# 3_Reinforcing_properties_Frequency_chara.net
KiCad netlist of a schematic drawn in Altium Designer
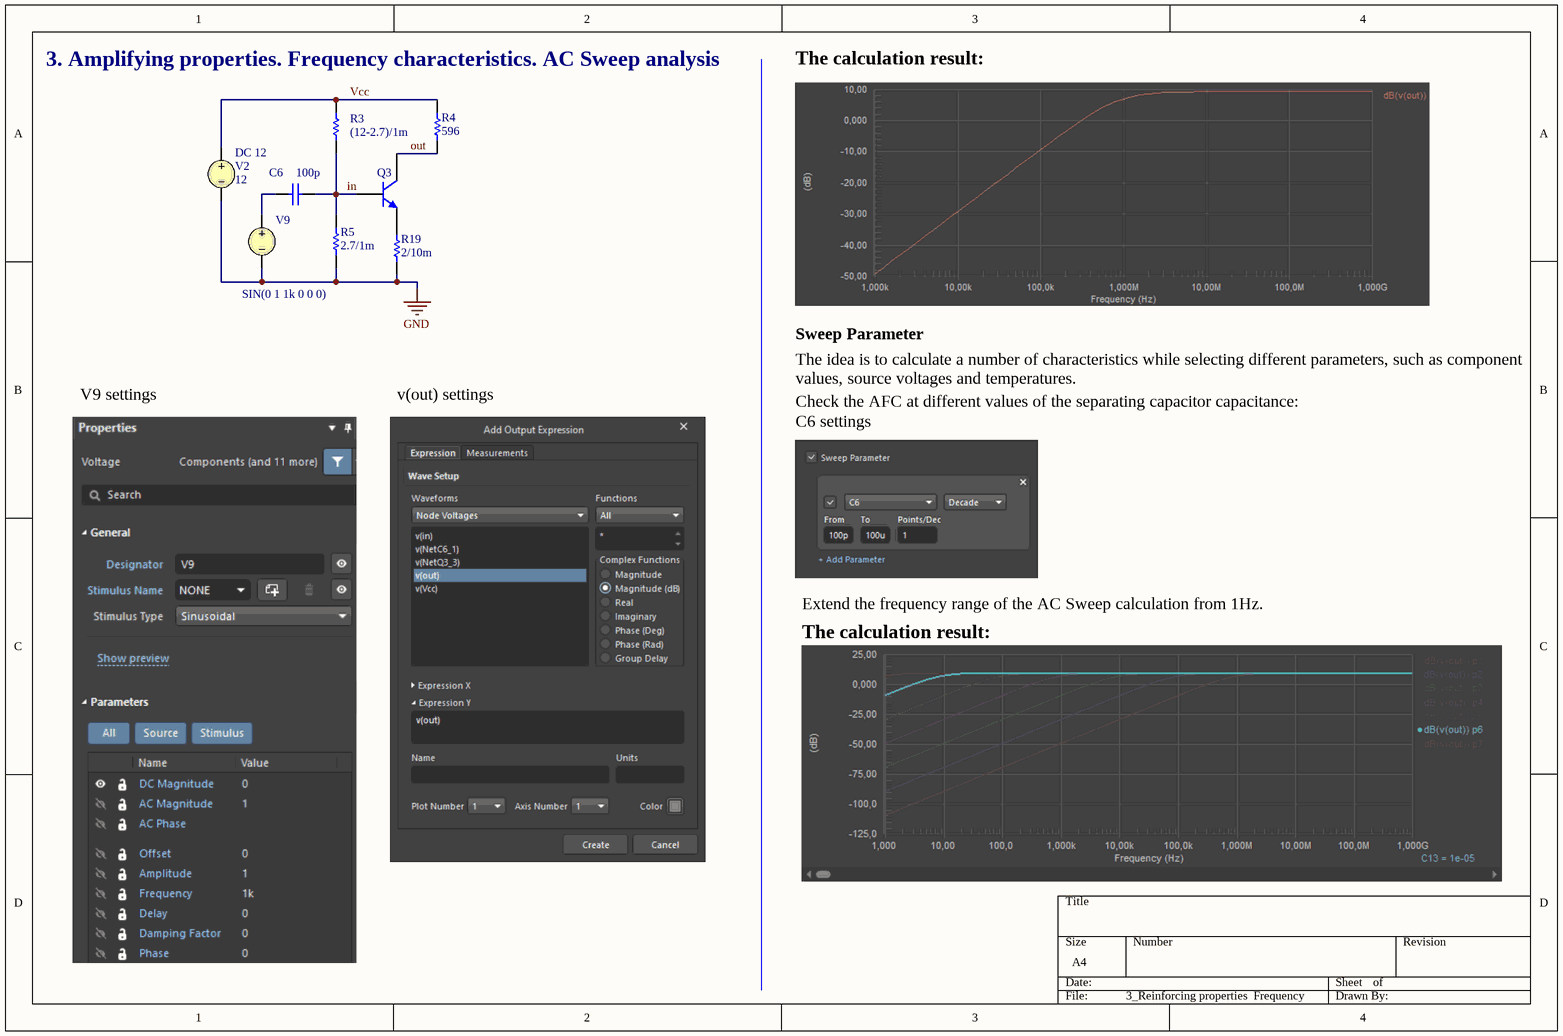
[diagram p0: 3_Reinforcing properties  Frequency characteristics.SchDoc]

(export (version "E")
  (design (tool "Eeschema 10.0.6"))
  (components
    (comp (ref "C6")
      (value "100p")
      (description "Capacitor")
      (libsource (lib "Simulation Generic Components") (part "Capacitor"))
    )
    (comp (ref "Q3")
      (value "Bipolar  NPN 3 Pins  Transistor  Modified Version of the Gummel-Poon Model")
      (libsource (lib "Simulation Generic Components") (part "BJT NPN_MGP"))
    )
    (comp (ref "R3")
      (value "(12-2.7)/1m")
      (description "Resistor")
      (libsource (lib "Simulation Generic Components") (part "Resistor"))
    )
    (comp (ref "R4")
      (value "596")
      (description "Resistor")
      (libsource (lib "Simulation Generic Components") (part "Resistor"))
    )
    (comp (ref "R5")
      (value "2.7/1m")
      (description "Resistor")
      (libsource (lib "Simulation Generic Components") (part "Resistor"))
    )
    (comp (ref "R19")
      (value "2/10m")
      (description "Resistor")
      (libsource (lib "Simulation Generic Components") (part "Resistor"))
    )
    (comp (ref "V2")
      (value "DC 12")
      (description "Voltage Source")
      (fields (field (name "ALTIUM_VALUE") "12") (field (name "PUBLISHER") "Altium Limited"))
      (libsource (lib "Simulation Generic Components") (part "VSRC"))
    )
    (comp (ref "V9")
      (value "SIN(0 1 1k 0 0 0)")
      (description "Voltage Source")
      (fields (field (name "PUBLISHER") "Altium Limited"))
      (libsource (lib "Simulation Generic Components") (part "VSRC"))
    )
  )
  (nets
    (net (code "1") (name "/Vcc") (class "Default")
      (node (ref "R3") (pin "2") (pinfunction "2_2") (pintype "passive"))
      (node (ref "R4") (pin "2") (pinfunction "2_2") (pintype "passive"))
      (node (ref "V2") (pin "1") (pinfunction "1_1") (pintype "passive"))
    )
    (net (code "2") (name "/in") (class "Default")
      (node (ref "C6") (pin "2") (pinfunction "2_2") (pintype "passive"))
      (node (ref "Q3") (pin "2") (pinfunction "B_2") (pintype "passive"))
      (node (ref "R3") (pin "1") (pinfunction "1_1") (pintype "passive"))
      (node (ref "R5") (pin "1") (pinfunction "1_1") (pintype "passive"))
    )
    (net (code "3") (name "/out") (class "Default")
      (node (ref "Q3") (pin "1") (pinfunction "C_1") (pintype "passive"))
      (node (ref "R4") (pin "1") (pinfunction "1_1") (pintype "passive"))
    )
    (net (code "4") (name "GND") (class "Default")
      (node (ref "R19") (pin "1") (pinfunction "1_1") (pintype "passive"))
      (node (ref "R5") (pin "2") (pinfunction "2_2") (pintype "passive"))
      (node (ref "V2") (pin "2") (pinfunction "2_2") (pintype "passive"))
      (node (ref "V9") (pin "2") (pinfunction "2_2") (pintype "passive"))
    )
    (net (code "5") (name "Net-(C6-Pad1)") (class "Default")
      (node (ref "C6") (pin "1") (pinfunction "1_1") (pintype "passive"))
      (node (ref "V9") (pin "1") (pinfunction "1_1") (pintype "passive"))
    )
    (net (code "6") (name "Net-(Q3-E)") (class "Default")
      (node (ref "Q3") (pin "3") (pinfunction "E_3") (pintype "passive"))
      (node (ref "R19") (pin "2") (pinfunction "2_2") (pintype "passive"))
    )
  )
)
